# MA1.net
KiCad netlist of a schematic drawn in EAGLE
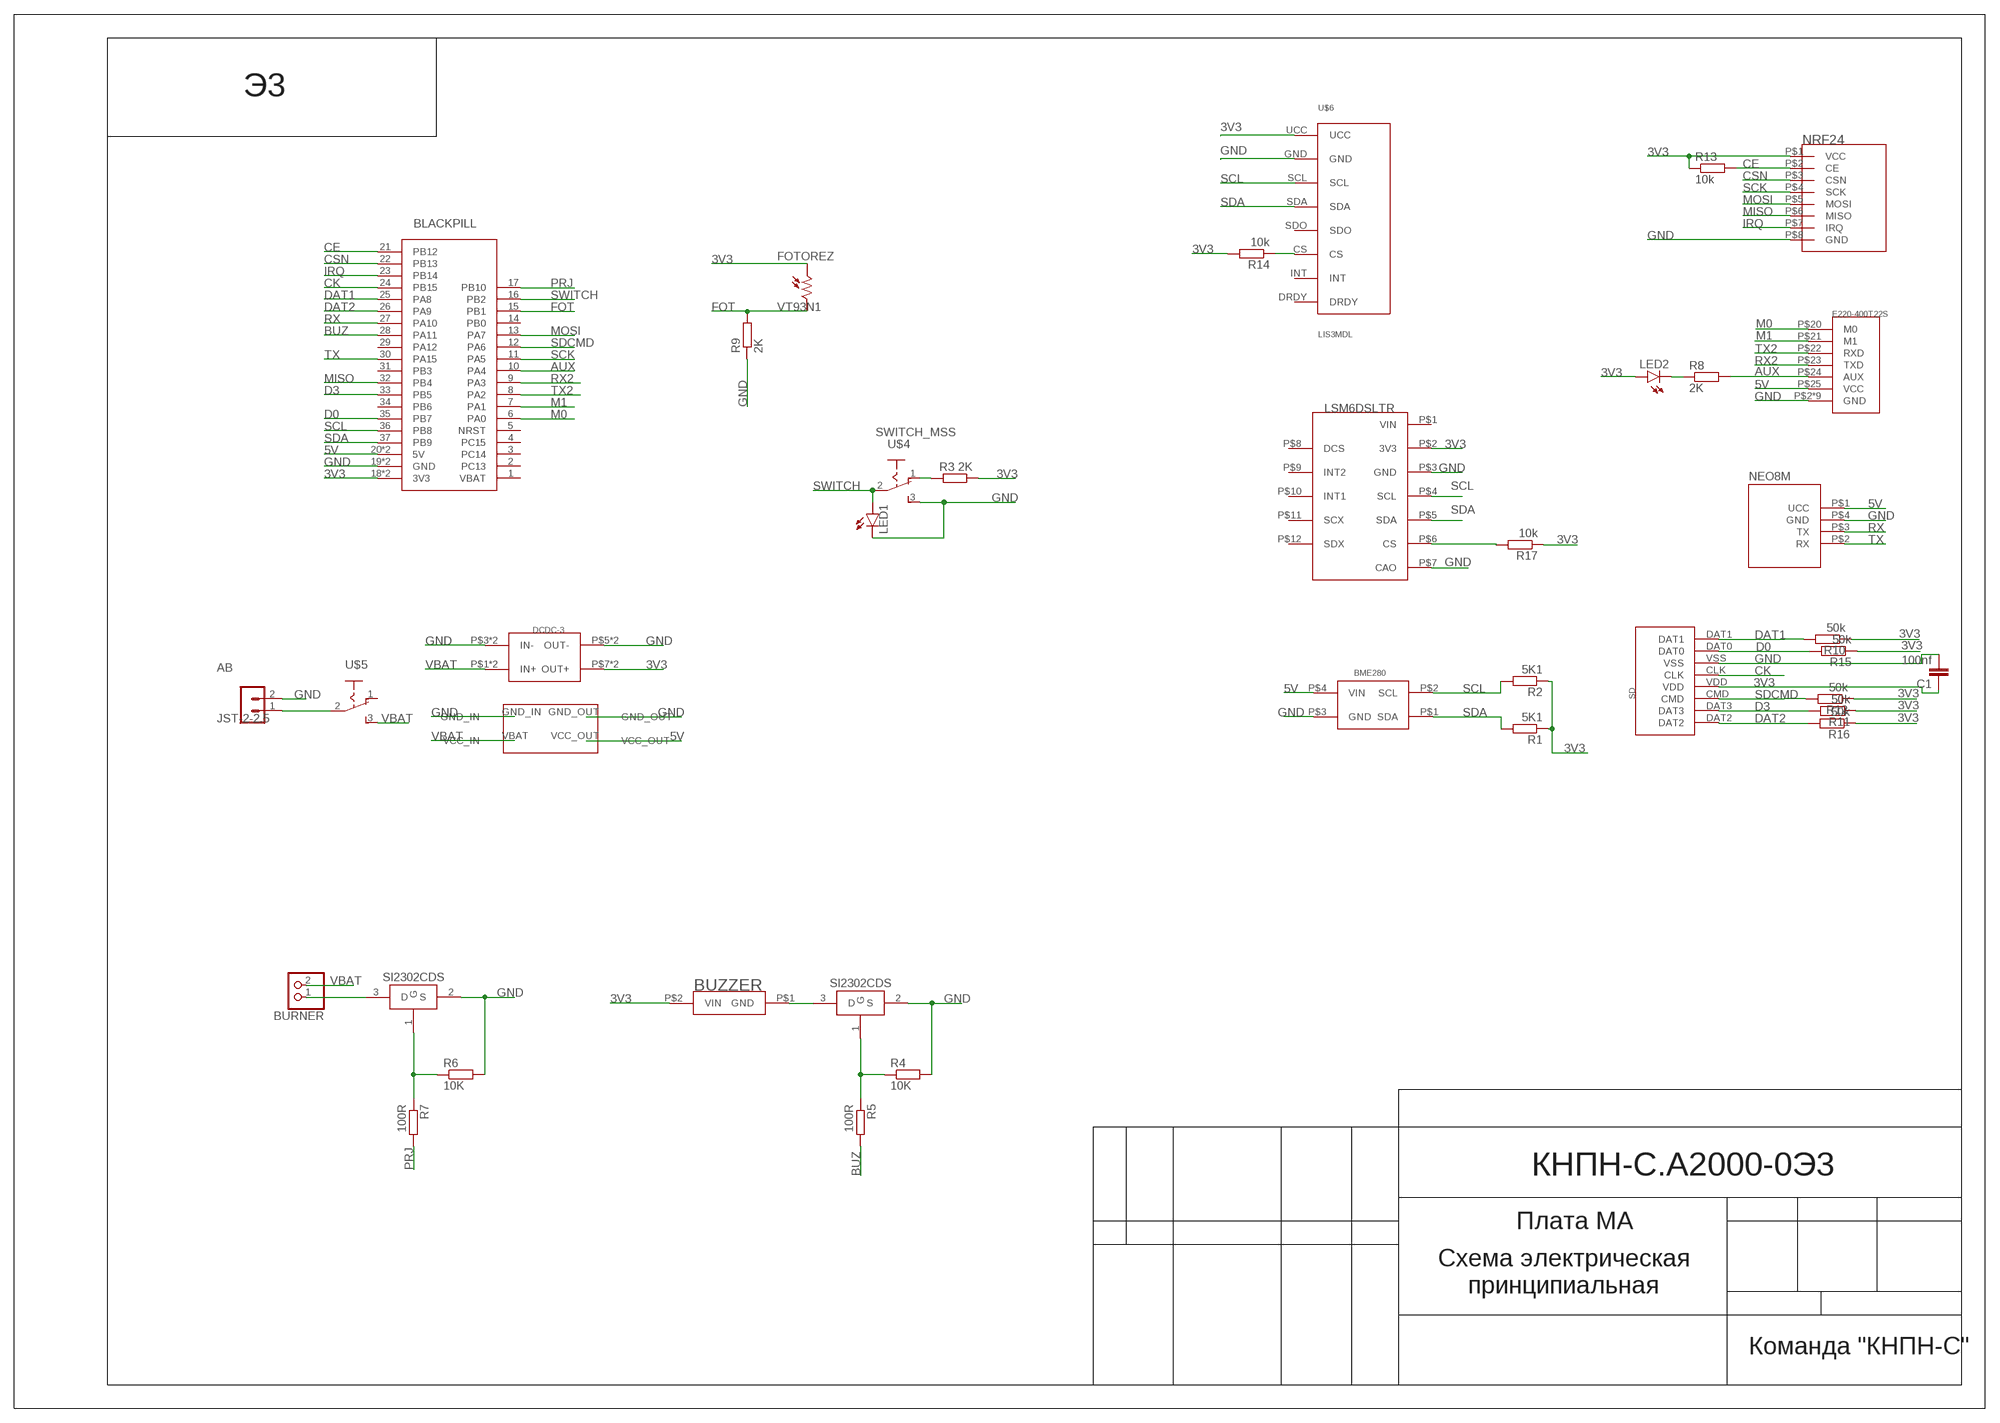
[diagram p0: schematic, sheet 1]

(export (version "E")
  (design (tool "Eeschema 10.0.6"))
  (components
    (comp (ref "AB")
      (value "JST-2-2.5")
      (footprint "eagle-import:JST-2-2.5")
      (libsource (lib "eagle-import") (part "JST-2-2.5"))
    )
    (comp (ref "BLACKPILL")
      (value "STM32F411_BOARD")
      (footprint "eagle-import:STM32F411_BOARD")
      (libsource (lib "eagle-import") (part "STM32F411_BOARD"))
    )
    (comp (ref "BME280")
      (value "BME280")
      (footprint "eagle-import:BME280")
      (libsource (lib "eagle-import") (part "BME280"))
    )
    (comp (ref "BURNER")
      (value "PINHD-1X2")
      (footprint "eagle-import:1X02")
      (libsource (lib "eagle-import") (part "PINHD-1X2"))
    )
    (comp (ref "BUZZER")
      (value "BUZZERS8R6")
      (footprint "eagle-import:BUZZER-S8R12")
      (libsource (lib "eagle-import") (part "BUZZERS8R6"))
    )
    (comp (ref "C1")
      (value "100nf")
      (footprint "eagle-import:C0603")
      (libsource (lib "eagle-import") (part "C-EUC0603"))
    )
    (comp (ref "DCDC-3")
      (value "MP1584-B")
      (footprint "eagle-import:MP1584-B")
      (libsource (lib "eagle-import") (part "MP1584-B"))
    )
    (comp (ref "E220-400T22S")
      (value "E220-400T22S")
      (footprint "eagle-import:E220-400T22S")
      (libsource (lib "eagle-import") (part "E220-400T22S"))
    )
    (comp (ref "FOTOREZ")
      (value "VT93N1")
      (footprint "eagle-import:VT93N1")
      (libsource (lib "eagle-import") (part "VT93N1"))
    )
    (comp (ref "LED1")
      (value "LEDCHIP-LED0603")
      (footprint "eagle-import:CHIP-LED0603")
      (libsource (lib "eagle-import") (part "LEDCHIP-LED0603"))
    )
    (comp (ref "LED2")
      (value "LEDCHIP-LED0603")
      (footprint "eagle-import:CHIP-LED0603")
      (libsource (lib "eagle-import") (part "LEDCHIP-LED0603"))
    )
    (comp (ref "LSM6DSLTR")
      (value "LSM6DS3-GY")
      (footprint "eagle-import:LSM6DS3-GY")
      (libsource (lib "eagle-import") (part "LSM6DS3-GY"))
    )
    (comp (ref "NEO8M")
      (value "GPS-NEO7M")
      (footprint "eagle-import:GPS-NEO7M")
      (libsource (lib "eagle-import") (part "GPS-NEO7M"))
    )
    (comp (ref "NRF24")
      (value "NRF24L01_ML01SP4")
      (footprint "eagle-import:NRF24L01_ML01SP4")
      (libsource (lib "eagle-import") (part "NRF24L01_ML01SP4"))
    )
    (comp (ref "R1")
      (value "5K1")
      (footprint "eagle-import:R0603")
      (libsource (lib "eagle-import") (part "R-EU_R0603"))
    )
    (comp (ref "R2")
      (value "5K1")
      (footprint "eagle-import:R0603")
      (libsource (lib "eagle-import") (part "R-EU_R0603"))
    )
    (comp (ref "R3")
      (value "2K")
      (footprint "eagle-import:R0603")
      (libsource (lib "eagle-import") (part "R-EU_R0603"))
    )
    (comp (ref "R4")
      (value "10K")
      (footprint "eagle-import:R0603")
      (libsource (lib "eagle-import") (part "R-EU_R0603"))
    )
    (comp (ref "R5")
      (value "100R")
      (footprint "eagle-import:R0603")
      (libsource (lib "eagle-import") (part "R-EU_R0603"))
    )
    (comp (ref "R6")
      (value "10K")
      (footprint "eagle-import:R0603")
      (libsource (lib "eagle-import") (part "R-EU_R0603"))
    )
    (comp (ref "R7")
      (value "100R")
      (footprint "eagle-import:R0603")
      (libsource (lib "eagle-import") (part "R-EU_R0603"))
    )
    (comp (ref "R8")
      (value "2K")
      (footprint "eagle-import:R0603")
      (libsource (lib "eagle-import") (part "R-EU_R0603"))
    )
    (comp (ref "R9")
      (value "2K")
      (footprint "eagle-import:R0603")
      (libsource (lib "eagle-import") (part "R-EU_R0603"))
    )
    (comp (ref "R10")
      (value "50k")
      (footprint "eagle-import:R0603")
      (libsource (lib "eagle-import") (part "R-EU_R0603"))
    )
    (comp (ref "R11")
      (value "50k")
      (footprint "eagle-import:R0603")
      (libsource (lib "eagle-import") (part "R-EU_R0603"))
    )
    (comp (ref "R12")
      (value "50k")
      (footprint "eagle-import:R0603")
      (libsource (lib "eagle-import") (part "R-EU_R0603"))
    )
    (comp (ref "R13")
      (value "10k")
      (footprint "eagle-import:R0603")
      (libsource (lib "eagle-import") (part "R-EU_R0603"))
    )
    (comp (ref "R14")
      (value "10k")
      (footprint "eagle-import:R0603")
      (libsource (lib "eagle-import") (part "R-EU_R0603"))
    )
    (comp (ref "R15")
      (value "50k")
      (footprint "eagle-import:R0603")
      (libsource (lib "eagle-import") (part "R-EU_R0603"))
    )
    (comp (ref "R16")
      (value "50k")
      (footprint "eagle-import:R0603")
      (libsource (lib "eagle-import") (part "R-EU_R0603"))
    )
    (comp (ref "R17")
      (value "10k")
      (footprint "eagle-import:R0603")
      (libsource (lib "eagle-import") (part "R-EU_R0603"))
    )
    (comp (ref "SD") (value "SD") (footprint "eagle-import:SD") (libsource (lib "eagle-import") (part "SD")))
    (comp (ref "U$1")
      (value "DS-DS_5V")
      (footprint "eagle-import:DS-DS_5V")
      (libsource (lib "eagle-import") (part "DS-DS_5V"))
    )
    (comp (ref "U$2")
      (value "SI2302CDS")
      (footprint "eagle-import:SOT23-3")
      (libsource (lib "eagle-import") (part "SI2302CDS"))
    )
    (comp (ref "U$3")
      (value "SI2302CDS")
      (footprint "eagle-import:SOT23-3")
      (libsource (lib "eagle-import") (part "SI2302CDS"))
    )
    (comp (ref "U$4")
      (value "SWITCH_MSS")
      (footprint "eagle-import:SWITCH_MSS")
      (libsource (lib "eagle-import") (part "SWITCH_MSS"))
    )
    (comp (ref "U$5")
      (value "UNICS-SWITCHSS_12D11")
      (footprint "eagle-import:SS_12D11")
      (libsource (lib "eagle-import") (part "UNICS-SWITCHSS_12D11"))
    )
    (comp (ref "U$6")
      (value "LIS3MDL")
      (footprint "eagle-import:LIS3MDL")
      (libsource (lib "eagle-import") (part "LIS3MDL"))
    )
  )
  (nets
    (net (code "1") (name "/3V3") (class "Default")
      (node (ref "BLACKPILL") (pin "18") (pinfunction "3V3_18") (pintype "bidirectional"))
      (node (ref "BLACKPILL") (pin "40") (pinfunction "3V3_40") (pintype "bidirectional"))
      (node (ref "BUZZER") (pin "P$2") (pinfunction "VIN_P$2") (pintype "bidirectional"))
      (node (ref "C1") (pin "1") (pinfunction "1_1") (pintype "passive"))
      (node (ref "DCDC-3") (pin "P$7") (pinfunction "OUT+_P$7") (pintype "bidirectional"))
      (node (ref "DCDC-3") (pin "P$8") (pinfunction "OUT+_P$8") (pintype "bidirectional"))
      (node (ref "FOTOREZ") (pin "P$1") (pinfunction "1_P$1") (pintype "passive"))
      (node (ref "LED2") (pin "A") (pinfunction "A_A") (pintype "passive"))
      (node (ref "LSM6DSLTR") (pin "P$2") (pinfunction "3V3_P$2") (pintype "bidirectional"))
      (node (ref "NRF24") (pin "P$1") (pinfunction "VCC_P$1") (pintype "bidirectional"))
      (node (ref "R1") (pin "1") (pinfunction "1_1") (pintype "passive"))
      (node (ref "R10") (pin "1") (pinfunction "1_1") (pintype "passive"))
      (node (ref "R11") (pin "1") (pinfunction "1_1") (pintype "passive"))
      (node (ref "R12") (pin "1") (pinfunction "1_1") (pintype "passive"))
      (node (ref "R13") (pin "1") (pinfunction "1_1") (pintype "passive"))
      (node (ref "R14") (pin "2") (pinfunction "2_2") (pintype "passive"))
      (node (ref "R15") (pin "1") (pinfunction "1_1") (pintype "passive"))
      (node (ref "R16") (pin "1") (pinfunction "1_1") (pintype "passive"))
      (node (ref "R17") (pin "1") (pinfunction "1_1") (pintype "passive"))
      (node (ref "R2") (pin "1") (pinfunction "1_1") (pintype "passive"))
      (node (ref "R3") (pin "1") (pinfunction "1_1") (pintype "passive"))
      (node (ref "SD") (pin "VDD") (pinfunction "VDD_VDD") (pintype "bidirectional"))
      (node (ref "U$6") (pin "UCC") (pinfunction "UCC_UCC") (pintype "bidirectional"))
    )
    (net (code "2") (name "/5V") (class "Default")
      (node (ref "BLACKPILL") (pin "20") (pinfunction "5V_20") (pintype "bidirectional"))
      (node (ref "BLACKPILL") (pin "38") (pinfunction "5V_38") (pintype "bidirectional"))
      (node (ref "BME280") (pin "P$4") (pinfunction "VIN_P$4") (pintype "bidirectional"))
      (node (ref "E220-400T22S") (pin "P$25") (pinfunction "VCC_P$25") (pintype "bidirectional"))
      (node (ref "NEO8M") (pin "P$1") (pinfunction "UCC_P$1") (pintype "bidirectional"))
      (node (ref "U$1") (pin "VCC_OUT") (pinfunction "VCC_OUT_VCC_OUT") (pintype "bidirectional"))
    )
    (net (code "3") (name "/AUX") (class "Default")
      (node (ref "BLACKPILL") (pin "10") (pinfunction "PA4_10") (pintype "bidirectional"))
      (node (ref "E220-400T22S") (pin "P$24") (pinfunction "AUX_P$24") (pintype "bidirectional"))
      (node (ref "R8") (pin "2") (pinfunction "2_2") (pintype "passive"))
    )
    (net (code "4") (name "/BUZ") (class "Default")
      (node (ref "BLACKPILL") (pin "28") (pinfunction "PA11_28") (pintype "bidirectional"))
      (node (ref "R5") (pin "2") (pinfunction "2_2") (pintype "passive"))
    )
    (net (code "5") (name "/CE") (class "Default")
      (node (ref "BLACKPILL") (pin "21") (pinfunction "PB12_21") (pintype "bidirectional"))
      (node (ref "NRF24") (pin "P$2") (pinfunction "CE_P$2") (pintype "bidirectional"))
      (node (ref "R13") (pin "2") (pinfunction "2_2") (pintype "passive"))
    )
    (net (code "6") (name "/CK") (class "Default")
      (node (ref "BLACKPILL") (pin "24") (pinfunction "PB15_24") (pintype "bidirectional"))
      (node (ref "SD") (pin "CLK") (pinfunction "CLK_CLK") (pintype "bidirectional"))
    )
    (net (code "7") (name "/CSN") (class "Default")
      (node (ref "BLACKPILL") (pin "22") (pinfunction "PB13_22") (pintype "bidirectional"))
      (node (ref "NRF24") (pin "P$3") (pinfunction "CSN_P$3") (pintype "bidirectional"))
    )
    (net (code "8") (name "/D0") (class "Default")
      (node (ref "BLACKPILL") (pin "35") (pinfunction "PB7_35") (pintype "bidirectional"))
      (node (ref "R15") (pin "2") (pinfunction "2_2") (pintype "passive"))
      (node (ref "SD") (pin "DAT0") (pinfunction "DAT0_DAT0") (pintype "bidirectional"))
    )
    (net (code "9") (name "/D3") (class "Default")
      (node (ref "BLACKPILL") (pin "33") (pinfunction "PB5_33") (pintype "bidirectional"))
      (node (ref "R11") (pin "2") (pinfunction "2_2") (pintype "passive"))
      (node (ref "SD") (pin "DAT3") (pinfunction "DAT3_DAT3") (pintype "bidirectional"))
    )
    (net (code "10") (name "/DAT1") (class "Default")
      (node (ref "BLACKPILL") (pin "25") (pinfunction "PA8_25") (pintype "bidirectional"))
      (node (ref "R10") (pin "2") (pinfunction "2_2") (pintype "passive"))
      (node (ref "SD") (pin "DAT1") (pinfunction "DAT1_DAT1") (pintype "bidirectional"))
    )
    (net (code "11") (name "/DAT2") (class "Default")
      (node (ref "BLACKPILL") (pin "26") (pinfunction "PA9_26") (pintype "bidirectional"))
      (node (ref "R16") (pin "2") (pinfunction "2_2") (pintype "passive"))
      (node (ref "SD") (pin "DAT2") (pinfunction "DAT2_DAT2") (pintype "bidirectional"))
    )
    (net (code "12") (name "/FOT") (class "Default")
      (node (ref "BLACKPILL") (pin "15") (pinfunction "PB1_15") (pintype "bidirectional"))
      (node (ref "FOTOREZ") (pin "P$2") (pinfunction "2_P$2") (pintype "passive"))
      (node (ref "R9") (pin "2") (pinfunction "2_2") (pintype "passive"))
    )
    (net (code "13") (name "/GND") (class "Default")
      (node (ref "AB") (pin "2") (pinfunction "2_2") (pintype "passive"))
      (node (ref "BLACKPILL") (pin "19") (pinfunction "GND_19") (pintype "bidirectional"))
      (node (ref "BLACKPILL") (pin "39") (pinfunction "GND_39") (pintype "bidirectional"))
      (node (ref "BME280") (pin "P$3") (pinfunction "GND_P$3") (pintype "bidirectional"))
      (node (ref "C1") (pin "2") (pinfunction "2_2") (pintype "passive"))
      (node (ref "DCDC-3") (pin "P$3") (pinfunction "IN-_P$3") (pintype "bidirectional"))
      (node (ref "DCDC-3") (pin "P$4") (pinfunction "IN-_P$4") (pintype "bidirectional"))
      (node (ref "DCDC-3") (pin "P$5") (pinfunction "OUT-_P$5") (pintype "bidirectional"))
      (node (ref "DCDC-3") (pin "P$6") (pinfunction "OUT-_P$6") (pintype "bidirectional"))
      (node (ref "E220-400T22S") (pin "P$11") (pinfunction "GND_P$11") (pintype "bidirectional"))
      (node (ref "E220-400T22S") (pin "P$13") (pinfunction "GND_P$13") (pintype "bidirectional"))
      (node (ref "E220-400T22S") (pin "P$14") (pinfunction "GND_P$14") (pintype "bidirectional"))
      (node (ref "E220-400T22S") (pin "P$15") (pinfunction "GND_P$15") (pintype "bidirectional"))
      (node (ref "E220-400T22S") (pin "P$16") (pinfunction "GND_P$16") (pintype "bidirectional"))
      (node (ref "E220-400T22S") (pin "P$19") (pinfunction "GND_P$19") (pintype "bidirectional"))
      (node (ref "E220-400T22S") (pin "P$2") (pinfunction "GND_P$2") (pintype "bidirectional"))
      (node (ref "E220-400T22S") (pin "P$26") (pinfunction "GND_P$26") (pintype "bidirectional"))
      (node (ref "E220-400T22S") (pin "P$8") (pinfunction "GND_P$8") (pintype "bidirectional"))
      (node (ref "LED1") (pin "C") (pinfunction "C_C") (pintype "passive"))
      (node (ref "LSM6DSLTR") (pin "P$3") (pinfunction "GND_P$3") (pintype "bidirectional"))
      (node (ref "LSM6DSLTR") (pin "P$7") (pinfunction "CAO_P$7") (pintype "bidirectional"))
      (node (ref "NEO8M") (pin "P$4") (pinfunction "GND_P$4") (pintype "bidirectional"))
      (node (ref "NRF24") (pin "P$8") (pinfunction "GND_P$8") (pintype "bidirectional"))
      (node (ref "R4") (pin "2") (pinfunction "2_2") (pintype "passive"))
      (node (ref "R6") (pin "2") (pinfunction "2_2") (pintype "passive"))
      (node (ref "R9") (pin "1") (pinfunction "1_1") (pintype "passive"))
      (node (ref "SD") (pin "VSS") (pinfunction "VSS_VSS") (pintype "bidirectional"))
      (node (ref "U$1") (pin "GND_IN") (pinfunction "GND_IN_GND_IN") (pintype "bidirectional"))
      (node (ref "U$1") (pin "GND_OUT") (pinfunction "GND_OUT_GND_OUT") (pintype "bidirectional"))
      (node (ref "U$2") (pin "2") (pinfunction "S_2") (pintype "bidirectional"))
      (node (ref "U$3") (pin "2") (pinfunction "S_2") (pintype "bidirectional"))
      (node (ref "U$4") (pin "3") (pinfunction "S_3") (pintype "passive"))
      (node (ref "U$6") (pin "GND") (pinfunction "GND_GND") (pintype "bidirectional"))
    )
    (net (code "14") (name "/IRQ") (class "Default")
      (node (ref "BLACKPILL") (pin "23") (pinfunction "PB14_23") (pintype "bidirectional"))
      (node (ref "NRF24") (pin "P$7") (pinfunction "IRQ_P$7") (pintype "bidirectional"))
    )
    (net (code "15") (name "/M0") (class "Default")
      (node (ref "BLACKPILL") (pin "6") (pinfunction "PA0_6") (pintype "bidirectional"))
      (node (ref "E220-400T22S") (pin "P$20") (pinfunction "M0_P$20") (pintype "bidirectional"))
    )
    (net (code "16") (name "/M1") (class "Default")
      (node (ref "BLACKPILL") (pin "7") (pinfunction "PA1_7") (pintype "bidirectional"))
      (node (ref "E220-400T22S") (pin "P$21") (pinfunction "M1_P$21") (pintype "bidirectional"))
    )
    (net (code "17") (name "/MISO") (class "Default")
      (node (ref "BLACKPILL") (pin "32") (pinfunction "PB4_32") (pintype "bidirectional"))
      (node (ref "NRF24") (pin "P$6") (pinfunction "MISO_P$6") (pintype "bidirectional"))
    )
    (net (code "18") (name "/MOSI") (class "Default")
      (node (ref "BLACKPILL") (pin "13") (pinfunction "PA7_13") (pintype "bidirectional"))
      (node (ref "NRF24") (pin "P$5") (pinfunction "MOSI_P$5") (pintype "bidirectional"))
    )
    (net (code "19") (name "/PRJ") (class "Default")
      (node (ref "BLACKPILL") (pin "17") (pinfunction "PB10_17") (pintype "bidirectional"))
      (node (ref "R7") (pin "2") (pinfunction "2_2") (pintype "passive"))
    )
    (net (code "20") (name "/RX") (class "Default")
      (node (ref "BLACKPILL") (pin "27") (pinfunction "PA10_27") (pintype "bidirectional"))
      (node (ref "NEO8M") (pin "P$3") (pinfunction "TX_P$3") (pintype "bidirectional"))
    )
    (net (code "21") (name "/RX2") (class "Default")
      (node (ref "BLACKPILL") (pin "9") (pinfunction "PA3_9") (pintype "bidirectional"))
      (node (ref "E220-400T22S") (pin "P$23") (pinfunction "TXD_P$23") (pintype "bidirectional"))
    )
    (net (code "22") (name "/SCK") (class "Default")
      (node (ref "BLACKPILL") (pin "11") (pinfunction "PA5_11") (pintype "bidirectional"))
      (node (ref "NRF24") (pin "P$4") (pinfunction "SCK_P$4") (pintype "bidirectional"))
    )
    (net (code "23") (name "/SCL") (class "Default")
      (node (ref "BLACKPILL") (pin "36") (pinfunction "PB8_36") (pintype "bidirectional"))
      (node (ref "BME280") (pin "P$2") (pinfunction "SCL_P$2") (pintype "bidirectional"))
      (node (ref "LSM6DSLTR") (pin "P$4") (pinfunction "SCL_P$4") (pintype "bidirectional"))
      (node (ref "R2") (pin "2") (pinfunction "2_2") (pintype "passive"))
      (node (ref "U$6") (pin "SCL") (pinfunction "SCL_SCL") (pintype "bidirectional"))
    )
    (net (code "24") (name "/SDA") (class "Default")
      (node (ref "BLACKPILL") (pin "37") (pinfunction "PB9_37") (pintype "bidirectional"))
      (node (ref "BME280") (pin "P$1") (pinfunction "SDA_P$1") (pintype "bidirectional"))
      (node (ref "LSM6DSLTR") (pin "P$5") (pinfunction "SDA_P$5") (pintype "bidirectional"))
      (node (ref "R1") (pin "2") (pinfunction "2_2") (pintype "passive"))
      (node (ref "U$6") (pin "SDA") (pinfunction "SDA_SDA") (pintype "bidirectional"))
    )
    (net (code "25") (name "/SDCMD") (class "Default")
      (node (ref "BLACKPILL") (pin "12") (pinfunction "PA6_12") (pintype "bidirectional"))
      (node (ref "R12") (pin "2") (pinfunction "2_2") (pintype "passive"))
      (node (ref "SD") (pin "CMD") (pinfunction "CMD_CMD") (pintype "bidirectional"))
    )
    (net (code "26") (name "/SWITCH") (class "Default")
      (node (ref "BLACKPILL") (pin "16") (pinfunction "PB2_16") (pintype "bidirectional"))
      (node (ref "LED1") (pin "A") (pinfunction "A_A") (pintype "passive"))
      (node (ref "U$4") (pin "2") (pinfunction "P_2") (pintype "passive"))
    )
    (net (code "27") (name "/TX") (class "Default")
      (node (ref "BLACKPILL") (pin "30") (pinfunction "PA15_30") (pintype "bidirectional"))
      (node (ref "NEO8M") (pin "P$2") (pinfunction "RX_P$2") (pintype "bidirectional"))
    )
    (net (code "28") (name "/TX2") (class "Default")
      (node (ref "BLACKPILL") (pin "8") (pinfunction "PA2_8") (pintype "bidirectional"))
      (node (ref "E220-400T22S") (pin "P$22") (pinfunction "RXD_P$22") (pintype "bidirectional"))
    )
    (net (code "29") (name "/VBAT") (class "Default")
      (node (ref "BURNER") (pin "2") (pinfunction "2_2") (pintype "passive"))
      (node (ref "DCDC-3") (pin "P$1") (pinfunction "IN+_P$1") (pintype "bidirectional"))
      (node (ref "DCDC-3") (pin "P$2") (pinfunction "IN+_P$2") (pintype "bidirectional"))
      (node (ref "U$1") (pin "VBAT") (pinfunction "VCC_IN_VBAT") (pintype "bidirectional"))
      (node (ref "U$5") (pin "3") (pinfunction "S_3") (pintype "passive"))
    )
    (net (code "30") (name "Net-(BUZZER-GND)") (class "Default")
      (node (ref "BUZZER") (pin "P$1") (pinfunction "GND_P$1") (pintype "bidirectional"))
      (node (ref "U$2") (pin "3") (pinfunction "D_3") (pintype "bidirectional"))
    )
    (net (code "31") (name "Net-(LED2-PadC)") (class "Default")
      (node (ref "LED2") (pin "C") (pinfunction "C_C") (pintype "passive"))
      (node (ref "R8") (pin "1") (pinfunction "1_1") (pintype "passive"))
    )
    (net (code "32") (name "Net-(LSM6DSLTR-CS)") (class "Default")
      (node (ref "LSM6DSLTR") (pin "P$6") (pinfunction "CS_P$6") (pintype "bidirectional"))
      (node (ref "R17") (pin "2") (pinfunction "2_2") (pintype "passive"))
    )
    (net (code "33") (name "Net-(R14-Pad1)") (class "Default")
      (node (ref "R14") (pin "1") (pinfunction "1_1") (pintype "passive"))
      (node (ref "U$6") (pin "CS") (pinfunction "CS_CS") (pintype "bidirectional"))
    )
    (net (code "34") (name "Net-(U$2-G)") (class "Default")
      (node (ref "R4") (pin "1") (pinfunction "1_1") (pintype "passive"))
      (node (ref "R5") (pin "1") (pinfunction "1_1") (pintype "passive"))
      (node (ref "U$2") (pin "1") (pinfunction "G_1") (pintype "bidirectional"))
    )
    (net (code "35") (name "Net-(U$3-D)") (class "Default")
      (node (ref "BURNER") (pin "1") (pinfunction "1_1") (pintype "passive"))
      (node (ref "U$3") (pin "3") (pinfunction "D_3") (pintype "bidirectional"))
    )
    (net (code "36") (name "Net-(U$3-G)") (class "Default")
      (node (ref "R6") (pin "1") (pinfunction "1_1") (pintype "passive"))
      (node (ref "R7") (pin "1") (pinfunction "1_1") (pintype "passive"))
      (node (ref "U$3") (pin "1") (pinfunction "G_1") (pintype "bidirectional"))
    )
    (net (code "37") (name "Net-(U$4-O)") (class "Default")
      (node (ref "R3") (pin "2") (pinfunction "2_2") (pintype "passive"))
      (node (ref "U$4") (pin "1") (pinfunction "O_1") (pintype "passive"))
    )
    (net (code "38") (name "Net-(U$5-P)") (class "Default")
      (node (ref "AB") (pin "1") (pinfunction "1_1") (pintype "passive"))
      (node (ref "U$5") (pin "2") (pinfunction "P_2") (pintype "passive"))
    )
    (net (code "39") (name "unconnected-(BLACKPILL-NRST-Pad5)") (class "Default")
      (node (ref "BLACKPILL") (pin "5") (pinfunction "NRST_5") (pintype "bidirectional"))
    )
    (net (code "40") (name "unconnected-(BLACKPILL-PA12-Pad29)") (class "Default")
      (node (ref "BLACKPILL") (pin "29") (pinfunction "PA12_29") (pintype "bidirectional"))
    )
    (net (code "41") (name "unconnected-(BLACKPILL-PB0-Pad14)") (class "Default")
      (node (ref "BLACKPILL") (pin "14") (pinfunction "PB0_14") (pintype "bidirectional"))
    )
    (net (code "42") (name "unconnected-(BLACKPILL-PB3-Pad31)") (class "Default")
      (node (ref "BLACKPILL") (pin "31") (pinfunction "PB3_31") (pintype "bidirectional"))
    )
    (net (code "43") (name "unconnected-(BLACKPILL-PB6-Pad34)") (class "Default")
      (node (ref "BLACKPILL") (pin "34") (pinfunction "PB6_34") (pintype "bidirectional"))
    )
    (net (code "44") (name "unconnected-(BLACKPILL-PC13-Pad2)") (class "Default")
      (node (ref "BLACKPILL") (pin "2") (pinfunction "PC13_2") (pintype "bidirectional"))
    )
    (net (code "45") (name "unconnected-(BLACKPILL-PC14-Pad3)") (class "Default")
      (node (ref "BLACKPILL") (pin "3") (pinfunction "PC14_3") (pintype "bidirectional"))
    )
    (net (code "46") (name "unconnected-(BLACKPILL-PC15-Pad4)") (class "Default")
      (node (ref "BLACKPILL") (pin "4") (pinfunction "PC15_4") (pintype "bidirectional"))
    )
    (net (code "47") (name "unconnected-(BLACKPILL-VBAT-Pad1)") (class "Default")
      (node (ref "BLACKPILL") (pin "1") (pinfunction "VBAT_1") (pintype "bidirectional"))
    )
    (net (code "48") (name "unconnected-(LSM6DSLTR-DCS-PadP$8)") (class "Default")
      (node (ref "LSM6DSLTR") (pin "P$8") (pinfunction "DCS_P$8") (pintype "bidirectional"))
    )
    (net (code "49") (name "unconnected-(LSM6DSLTR-INT1-PadP$10)") (class "Default")
      (node (ref "LSM6DSLTR") (pin "P$10") (pinfunction "INT1_P$10") (pintype "bidirectional"))
    )
    (net (code "50") (name "unconnected-(LSM6DSLTR-INT2-PadP$9)") (class "Default")
      (node (ref "LSM6DSLTR") (pin "P$9") (pinfunction "INT2_P$9") (pintype "bidirectional"))
    )
    (net (code "51") (name "unconnected-(LSM6DSLTR-SCX-PadP$11)") (class "Default")
      (node (ref "LSM6DSLTR") (pin "P$11") (pinfunction "SCX_P$11") (pintype "bidirectional"))
    )
    (net (code "52") (name "unconnected-(LSM6DSLTR-SDX-PadP$12)") (class "Default")
      (node (ref "LSM6DSLTR") (pin "P$12") (pinfunction "SDX_P$12") (pintype "bidirectional"))
    )
    (net (code "53") (name "unconnected-(LSM6DSLTR-VIN-PadP$1)") (class "Default")
      (node (ref "LSM6DSLTR") (pin "P$1") (pinfunction "VIN_P$1") (pintype "bidirectional"))
    )
    (net (code "54") (name "unconnected-(U$5-O-Pad1)") (class "Default")
      (node (ref "U$5") (pin "1") (pinfunction "O_1") (pintype "passive"))
    )
    (net (code "55") (name "unconnected-(U$6-PadDRDY)") (class "Default")
      (node (ref "U$6") (pin "DRDY") (pinfunction "DRDY_DRDY") (pintype "bidirectional"))
    )
    (net (code "56") (name "unconnected-(U$6-PadINT)") (class "Default")
      (node (ref "U$6") (pin "INT") (pinfunction "INT_INT") (pintype "bidirectional"))
    )
    (net (code "57") (name "unconnected-(U$6-PadSDO)") (class "Default")
      (node (ref "U$6") (pin "SDO") (pinfunction "SDO_SDO") (pintype "bidirectional"))
    )
  )
)
